# Power_block.net
KiCad netlist of a schematic drawn in Altium Designer
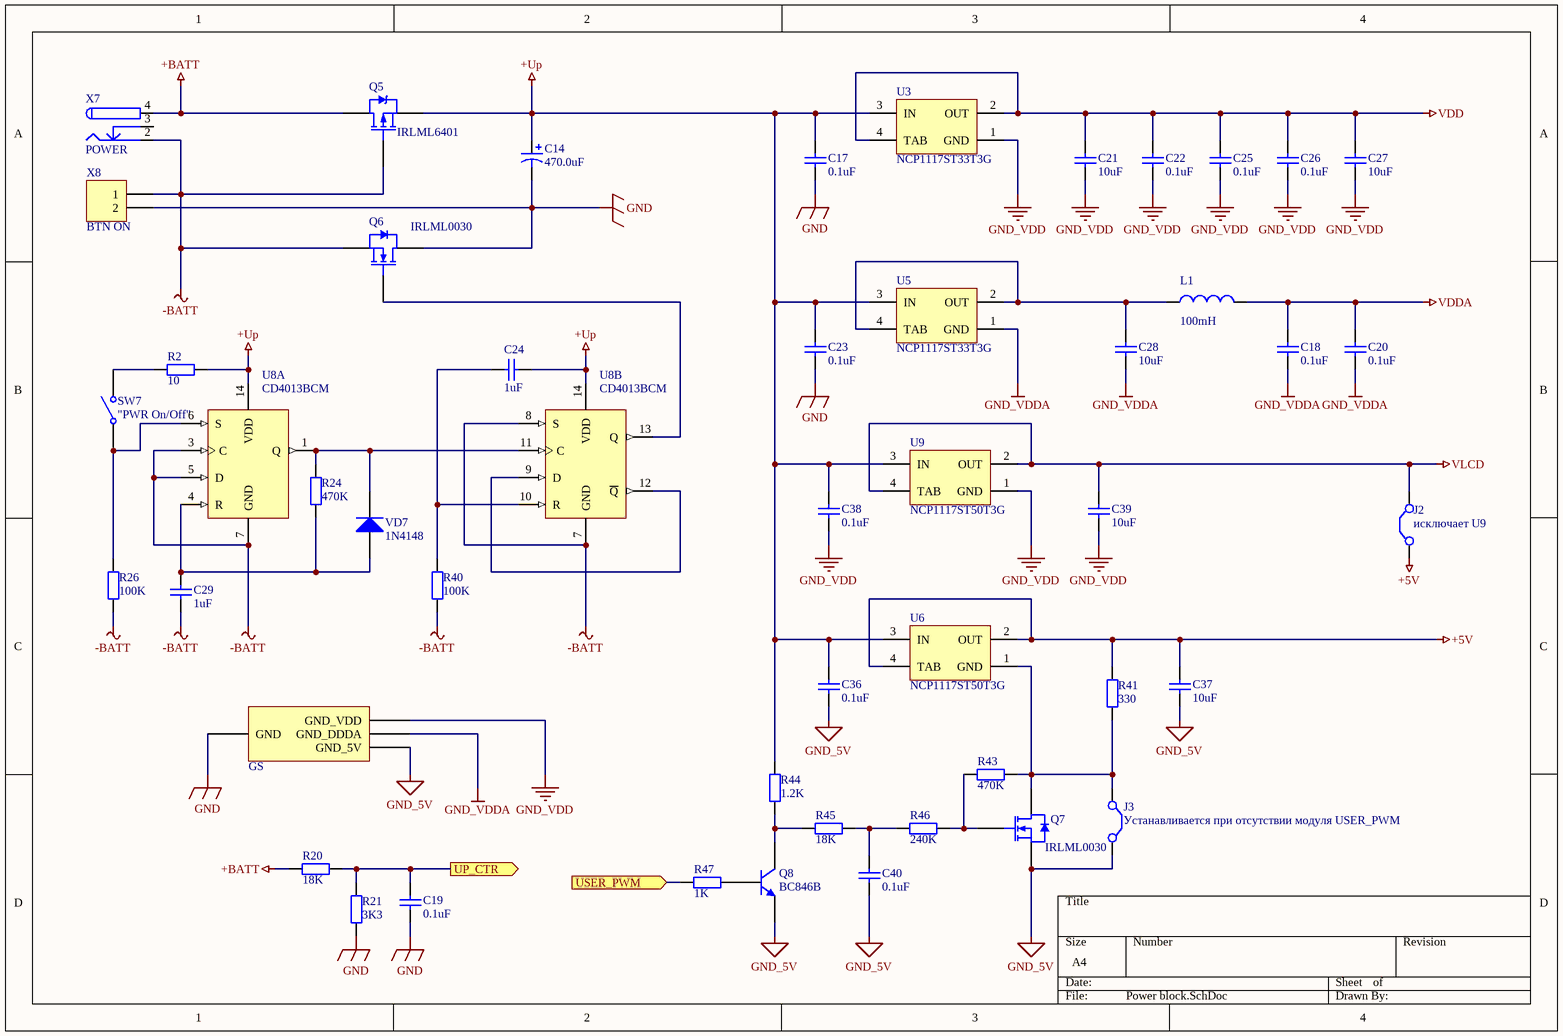
[diagram p0: Power block.SchDoc]

(export (version "E")
  (design (tool "Eeschema 10.0.6"))
  (components
    (comp (ref "C14")
      (value "470.0uF")
      (footprint "Capacitor-10x12.5-lyingR")
      (description "Polarized Capacitor (Radial)")
      (fields (field (name "PUBLISHER") "Altium Limited"))
      (libsource (lib "Quasar ARM") (part "Cap Pol1"))
    )
    (comp (ref "C17")
      (value "0.1uF")
      (footprint "1206_SMD_Capacitor")
      (description "Capacitor")
      (fields (field (name "PUBLISHER") "Altium Limited"))
      (libsource (lib "Quasar ARM") (part "Capacitor SMD"))
    )
    (comp (ref "C18")
      (value "0.1uF")
      (footprint "1206_SMD_Capacitor")
      (description "Capacitor")
      (fields (field (name "PUBLISHER") "Altium Limited"))
      (libsource (lib "Quasar ARM") (part "Capacitor SMD"))
    )
    (comp (ref "C19")
      (value "0.1uF")
      (footprint "1206_SMD_Capacitor")
      (description "Capacitor")
      (fields (field (name "PUBLISHER") "Altium Limited"))
      (libsource (lib "Quasar ARM") (part "Capacitor SMD"))
    )
    (comp (ref "C20")
      (value "0.1uF")
      (footprint "1206_SMD_Capacitor")
      (description "Capacitor")
      (fields (field (name "PUBLISHER") "Altium Limited"))
      (libsource (lib "Quasar ARM") (part "Capacitor SMD"))
    )
    (comp (ref "C21")
      (value "10uF")
      (footprint "1206_SMD_Capacitor")
      (description "Capacitor")
      (fields (field (name "PUBLISHER") "Altium Limited"))
      (libsource (lib "Quasar ARM") (part "Capacitor SMD"))
    )
    (comp (ref "C22")
      (value "0.1uF")
      (footprint "0805")
      (description "Capacitor")
      (fields (field (name "PUBLISHER") "Altium Limited"))
      (libsource (lib "Quasar ARM") (part "Capacitor SMD"))
    )
    (comp (ref "C23")
      (value "0.1uF")
      (footprint "1206_SMD_Capacitor")
      (description "Capacitor")
      (fields (field (name "PUBLISHER") "Altium Limited"))
      (libsource (lib "Quasar ARM") (part "Capacitor SMD"))
    )
    (comp (ref "C24")
      (value "1uF")
      (footprint "1206_SMD_Capacitor")
      (description "Capacitor")
      (fields (field (name "PUBLISHER") "Altium Limited"))
      (libsource (lib "Quasar ARM") (part "Capacitor SMD"))
    )
    (comp (ref "C25")
      (value "0.1uF")
      (footprint "0805")
      (description "Capacitor")
      (fields (field (name "PUBLISHER") "Altium Limited"))
      (libsource (lib "Quasar ARM") (part "Capacitor SMD"))
    )
    (comp (ref "C26")
      (value "0.1uF")
      (footprint "0805")
      (description "Capacitor")
      (fields (field (name "PUBLISHER") "Altium Limited"))
      (libsource (lib "Quasar ARM") (part "Capacitor SMD"))
    )
    (comp (ref "C27")
      (value "10uF")
      (footprint "1206_SMD_Capacitor")
      (description "Capacitor")
      (fields (field (name "PUBLISHER") "Altium Limited"))
      (libsource (lib "Quasar ARM") (part "Capacitor SMD"))
    )
    (comp (ref "C28")
      (value "10uF")
      (footprint "1206_SMD_Capacitor")
      (description "Capacitor")
      (fields (field (name "PUBLISHER") "Altium Limited"))
      (libsource (lib "Quasar ARM") (part "Capacitor SMD"))
    )
    (comp (ref "C29")
      (value "1uF")
      (footprint "1206_SMD_Capacitor")
      (description "Capacitor")
      (fields (field (name "PUBLISHER") "Altium Limited"))
      (libsource (lib "Quasar ARM") (part "Capacitor SMD"))
    )
    (comp (ref "C36")
      (value "0.1uF")
      (footprint "1206_SMD_Capacitor")
      (description "Capacitor")
      (fields (field (name "PUBLISHER") "Altium Limited"))
      (libsource (lib "Quasar ARM") (part "Capacitor SMD"))
    )
    (comp (ref "C37")
      (value "10uF")
      (footprint "1206_SMD_Capacitor")
      (description "Capacitor")
      (fields (field (name "PUBLISHER") "Altium Limited"))
      (libsource (lib "Quasar ARM") (part "Capacitor SMD"))
    )
    (comp (ref "C38")
      (value "0.1uF")
      (footprint "1206_SMD_Capacitor")
      (description "Capacitor")
      (fields (field (name "PUBLISHER") "Altium Limited"))
      (libsource (lib "Quasar ARM") (part "Capacitor SMD"))
    )
    (comp (ref "C39")
      (value "10uF")
      (footprint "1206_SMD_Capacitor")
      (description "Capacitor")
      (fields (field (name "PUBLISHER") "Altium Limited"))
      (libsource (lib "Quasar ARM") (part "Capacitor SMD"))
    )
    (comp (ref "C40")
      (value "0.1uF")
      (footprint "1206_SMD_Capacitor")
      (description "Capacitor")
      (fields (field (name "PUBLISHER") "Altium Limited"))
      (libsource (lib "Quasar ARM") (part "Capacitor SMD"))
    )
    (comp (ref "GS")
      (value "Ground setter")
      (footprint "GND_POINT")
      (libsource (lib "Quasar ARM") (part "Ground setter"))
    )
    (comp (ref "J2")
      (value "исключает U9")
      (footprint "1206_SMD_JUMPER")
      (description "Jumper Wire")
      (fields (field (name "PUBLISHER") "Altium Limited"))
      (libsource (lib "Quasar ARM") (part "Jumper"))
    )
    (comp (ref "J3")
      (value "Устанавливается при отсутствии модуля USER_PWM")
      (footprint "1206_SMD_Resistor")
      (description "Jumper Wire")
      (fields (field (name "PUBLISHER") "Altium Limited"))
      (libsource (lib "Quasar ARM") (part "Jumper"))
    )
    (comp (ref "L1")
      (value "100mH")
      (footprint "1210")
      (description "Inductor")
      (fields (field (name "PUBLISHER") "Altium Limited"))
      (libsource (lib "Quasar ARM") (part "Inductor"))
    )
    (comp (ref "Q5")
      (value "IRLML6401")
      (footprint "SOT23_N")
      (description "HEXFET Power MOSFET")
      (fields (field (name "PUBLISHER") "Altium Limited"))
      (libsource (lib "Quasar ARM") (part "IRLML6401"))
    )
    (comp (ref "Q6")
      (value "IRLML0030")
      (footprint "SOT23_N")
      (description "HEXFET Power MOSFET")
      (fields (field (name "PUBLISHER") "Altium Limited"))
      (libsource (lib "Quasar ARM") (part "2N7002"))
    )
    (comp (ref "Q7")
      (value "IRLML0030")
      (footprint "SOT23_N")
      (description "HEXFET Power MOSFET")
      (fields (field (name "PUBLISHER") "Altium Limited"))
      (libsource (lib "Quasar ARM") (part "2N7002"))
    )
    (comp (ref "Q8")
      (value "BC846B")
      (footprint "SOT23_N")
      (description "NPN General-purpose Transistor")
      (fields (field (name "PUBLISHER") "Altium Limited"))
      (libsource (lib "Quasar ARM") (part "BC846B"))
    )
    (comp (ref "R2")
      (value "10")
      (footprint "1206_SMD_Resistor")
      (description "Resistor")
      (fields (field (name "PUBLISHER") "Dmitry Kuzmin"))
      (libsource (lib "") (part "Resistor_1"))
    )
    (comp (ref "R20")
      (value "18K")
      (footprint "1206_SMD_Resistor")
      (description "Resistor")
      (fields (field (name "PUBLISHER") "Altium Limited"))
      (libsource (lib "") (part "Resistor_1"))
    )
    (comp (ref "R21")
      (value "3K3")
      (footprint "1206_SMD_Resistor")
      (description "Resistor")
      (fields (field (name "PUBLISHER") "Altium Limited"))
      (libsource (lib "") (part "Resistor_2"))
    )
    (comp (ref "R24")
      (value "470K")
      (footprint "1206_SMD_Resistor")
      (description "Resistor")
      (fields (field (name "PUBLISHER") "Dmitry Kuzmin"))
      (libsource (lib "") (part "Resistor_2"))
    )
    (comp (ref "R26")
      (value "100K")
      (footprint "1206_SMD_Resistor")
      (description "Resistor")
      (fields (field (name "PUBLISHER") "Dmitry Kuzmin"))
      (libsource (lib "") (part "Resistor_2"))
    )
    (comp (ref "R40")
      (value "100K")
      (footprint "1206_SMD_Resistor")
      (description "Resistor")
      (fields (field (name "PUBLISHER") "Dmitry Kuzmin"))
      (libsource (lib "") (part "Resistor_2"))
    )
    (comp (ref "R41")
      (value "330")
      (footprint "1206_SMD_Resistor")
      (description "Resistor")
      (fields (field (name "PUBLISHER") "Dmitry Kuzmin"))
      (libsource (lib "") (part "Resistor_2"))
    )
    (comp (ref "R43")
      (value "470K")
      (footprint "1206_SMD_Resistor")
      (description "Resistor")
      (fields (field (name "PUBLISHER") "Dmitry Kuzmin"))
      (libsource (lib "Quasar ARM") (part "Resistor"))
    )
    (comp (ref "R44")
      (value "1.2K")
      (footprint "1206_SMD_Resistor")
      (description "Resistor")
      (fields (field (name "PUBLISHER") "Dmitry Kuzmin"))
      (libsource (lib "") (part "Resistor_2"))
    )
    (comp (ref "R45")
      (value "18K")
      (footprint "1206_SMD_Resistor")
      (description "Resistor")
      (fields (field (name "PUBLISHER") "Dmitry Kuzmin"))
      (libsource (lib "") (part "Resistor_1"))
    )
    (comp (ref "R46")
      (value "240K")
      (footprint "1206_SMD_Resistor")
      (description "Resistor")
      (fields (field (name "PUBLISHER") "Dmitry Kuzmin"))
      (libsource (lib "") (part "Resistor_1"))
    )
    (comp (ref "R47")
      (value "1K")
      (footprint "1206_SMD_Resistor")
      (description "Resistor")
      (fields (field (name "PUBLISHER") "Dmitry Kuzmin"))
      (libsource (lib "") (part "Resistor_1"))
    )
    (comp (ref "SW7")
      (value "\"PWR On/Off\"")
      (footprint "KAN1211")
      (description "Single-Pole, Single-Throw Switch")
      (fields (field (name "PUBLISHER") "Altium Limited"))
      (libsource (lib "Quasar ARM") (part "TACT Switch"))
    )
    (comp (ref "U3")
      (value "NCP1117ST33T3G")
      (footprint "SOT-223")
      (description "LDO стабилизатор 3.3 V, 1 A, падение 1.2 V, Uвх до 20 V, 0..+125°C, 1%")
      (fields
        (field (name "PARTNUMBER") "LM1117S-3.3")
        (field (name "MANUFACTURER") "National Semiconductor")
        (field (name "PUBLISHER") "Altium Limited")
      )
      (libsource (lib "Quasar ARM_1") (part "NCP1117ST33"))
    )
    (comp (ref "U5")
      (value "NCP1117ST33T3G")
      (footprint "SOT-223")
      (description "LDO стабилизатор 3.3 V, 1 A, падение 1.2 V, Uвх до 20 V, 0..+125°C, 1%")
      (fields
        (field (name "PARTNUMBER") "LM1117S-3.3")
        (field (name "MANUFACTURER") "National Semiconductor")
        (field (name "PUBLISHER") "Altium Limited")
      )
      (libsource (lib "Quasar ARM_1") (part "NCP1117ST33"))
    )
    (comp (ref "U6")
      (value "NCP1117ST50T3G")
      (footprint "SOT-223")
      (description "LDO стабилизатор 5.0 V, 1 A, падение 1.2 V, Uвх до 20 V, 0..+125°C, 1%")
      (fields
        (field (name "PARTNUMBER") "LM1117S-5.0")
        (field (name "MANUFACTURER") "National Semiconductor")
        (field (name "PUBLISHER") "Altium Limited")
      )
      (libsource (lib "Quasar ARM_1") (part "NCP1117ST50"))
    )
    (comp (ref "U8")
      (value "CD4013BCM")
      (footprint "M14A_M")
      (description "Dual D-Type Flip-Flop")
      (fields (field (name "PUBLISHER") "Altium Limited"))
      (libsource (lib "") (part "CD4013BCM_1"))
    )
    (comp (ref "U9")
      (value "NCP1117ST50T3G")
      (footprint "SOT-223")
      (description "LDO стабилизатор 5.0 V, 1 A, падение 1.2 V, Uвх до 20 V, 0..+125°C, 1%")
      (fields
        (field (name "PARTNUMBER") "LM1117S-5.0")
        (field (name "MANUFACTURER") "National Semiconductor")
        (field (name "PUBLISHER") "Altium Limited")
      )
      (libsource (lib "Quasar ARM_1") (part "NCP1117ST50"))
    )
    (comp (ref "VD7")
      (value "1N4148")
      (footprint "SOD-323")
      (description "High Conductance Fast Diode")
      (fields (field (name "PUBLISHER") "Altium Limited"))
      (libsource (lib "Quasar ARM") (part "1N4148"))
    )
    (comp (ref "X7")
      (value "POWER")
      (footprint "DC-044")
      (description "Low Voltage Power Supply Connector")
      (fields (field (name "PUBLISHER") "Altium Limited"))
      (libsource (lib "Quasar ARM") (part "DC-044"))
    )
    (comp (ref "X8")
      (value "BTN ON")
      (footprint "HDR1X2")
      (description "Header, 2-Pin")
      (fields (field (name "PUBLISHER") "Altium Limited"))
      (libsource (lib "Quasar ARM") (part "Header 2"))
    )
  )
  (nets
    (net (code "1") (name "+5V") (class "Default")
      (node (ref "C37") (pin "2") (pinfunction "2_2") (pintype "passive"))
      (node (ref "J2") (pin "1") (pinfunction "C1_1") (pintype "passive"))
      (node (ref "R41") (pin "2") (pinfunction "2_2") (pintype "passive"))
      (node (ref "U6") (pin "2") (pinfunction "OUT_2") (pintype "power_in"))
      (node (ref "U6") (pin "4") (pinfunction "TAB_4") (pintype "power_in"))
    )
    (net (code "2") (name "+BATT") (class "Default")
      (node (ref "Q5") (pin "3") (pinfunction "D_3") (pintype "passive"))
      (node (ref "R20") (pin "1") (pinfunction "1_1") (pintype "passive"))
      (node (ref "X7") (pin "4") (pinfunction "4_4") (pintype "power_in"))
    )
    (net (code "3") (name "+Up") (class "Default")
      (node (ref "C14") (pin "1") (pinfunction "1_1") (pintype "passive"))
      (node (ref "C17") (pin "2") (pinfunction "2_2") (pintype "passive"))
      (node (ref "C23") (pin "2") (pinfunction "2_2") (pintype "passive"))
      (node (ref "C24") (pin "2") (pinfunction "2_2") (pintype "passive"))
      (node (ref "C36") (pin "2") (pinfunction "2_2") (pintype "passive"))
      (node (ref "C38") (pin "2") (pinfunction "2_2") (pintype "passive"))
      (node (ref "Q5") (pin "2") (pinfunction "S_2") (pintype "passive"))
      (node (ref "R2") (pin "2") (pinfunction "2_2") (pintype "passive"))
      (node (ref "R44") (pin "2") (pinfunction "2_2") (pintype "passive"))
      (node (ref "U3") (pin "3") (pinfunction "IN_3") (pintype "power_in"))
      (node (ref "U5") (pin "3") (pinfunction "IN_3") (pintype "power_in"))
      (node (ref "U6") (pin "3") (pinfunction "IN_3") (pintype "power_in"))
      (node (ref "U8") (pin "14") (pinfunction "VDD_14") (pintype "power_in"))
      (node (ref "U9") (pin "3") (pinfunction "IN_3") (pintype "power_in"))
    )
    (net (code "4") (name "-BATT") (class "Default")
      (node (ref "C29") (pin "1") (pinfunction "1_1") (pintype "passive"))
      (node (ref "Q5") (pin "1") (pinfunction "G_1") (pintype "passive"))
      (node (ref "Q6") (pin "2") (pinfunction "S_2") (pintype "passive"))
      (node (ref "R26") (pin "1") (pinfunction "1_1") (pintype "passive"))
      (node (ref "R40") (pin "1") (pinfunction "1_1") (pintype "passive"))
      (node (ref "U8") (pin "3") (pinfunction "C_3") (pintype "input"))
      (node (ref "U8") (pin "5") (pinfunction "D_5") (pintype "input"))
      (node (ref "U8") (pin "7") (pinfunction "GND_7") (pintype "power_in"))
      (node (ref "U8") (pin "8") (pinfunction "S_8") (pintype "input"))
      (node (ref "X7") (pin "2") (pinfunction "2_2") (pintype "power_in"))
      (node (ref "X8") (pin "1") (pinfunction "1_1") (pintype "passive"))
    )
    (net (code "5") (name "/UP_CTR") (class "Default")
      (node (ref "C19") (pin "2") (pinfunction "2_2") (pintype "passive"))
      (node (ref "R20") (pin "2") (pinfunction "2_2") (pintype "passive"))
      (node (ref "R21") (pin "2") (pinfunction "2_2") (pintype "passive"))
    )
    (net (code "6") (name "/USER_PWM") (class "Default")
      (node (ref "R47") (pin "1") (pinfunction "1_1") (pintype "passive"))
    )
    (net (code "7") (name "GND") (class "Default")
      (node (ref "C14") (pin "2") (pinfunction "2_2") (pintype "passive"))
      (node (ref "C17") (pin "1") (pinfunction "1_1") (pintype "passive"))
      (node (ref "C19") (pin "1") (pinfunction "1_1") (pintype "passive"))
      (node (ref "C23") (pin "1") (pinfunction "1_1") (pintype "passive"))
      (node (ref "GS") (pin "1") (pinfunction "GND_1") (pintype "passive"))
      (node (ref "Q6") (pin "3") (pinfunction "D_3") (pintype "passive"))
      (node (ref "R21") (pin "1") (pinfunction "1_1") (pintype "passive"))
      (node (ref "X8") (pin "2") (pinfunction "2_2") (pintype "passive"))
    )
    (net (code "8") (name "GND_5V") (class "Default")
      (node (ref "C36") (pin "1") (pinfunction "1_1") (pintype "passive"))
      (node (ref "C37") (pin "1") (pinfunction "1_1") (pintype "passive"))
      (node (ref "C40") (pin "1") (pinfunction "1_1") (pintype "passive"))
      (node (ref "GS") (pin "4") (pinfunction "GND_5V_4") (pintype "passive"))
      (node (ref "J3") (pin "2") (pinfunction "C2_2") (pintype "passive"))
      (node (ref "Q7") (pin "2") (pinfunction "S_2") (pintype "passive"))
      (node (ref "Q8") (pin "2") (pinfunction "E_2") (pintype "passive"))
    )
    (net (code "9") (name "GND_VDD") (class "Default")
      (node (ref "C21") (pin "1") (pinfunction "1_1") (pintype "passive"))
      (node (ref "C22") (pin "1") (pinfunction "1_1") (pintype "passive"))
      (node (ref "C25") (pin "1") (pinfunction "1_1") (pintype "passive"))
      (node (ref "C26") (pin "1") (pinfunction "1_1") (pintype "passive"))
      (node (ref "C27") (pin "1") (pinfunction "1_1") (pintype "passive"))
      (node (ref "C38") (pin "1") (pinfunction "1_1") (pintype "passive"))
      (node (ref "C39") (pin "1") (pinfunction "1_1") (pintype "passive"))
      (node (ref "GS") (pin "2") (pinfunction "GND_VDD_2") (pintype "passive"))
      (node (ref "U3") (pin "1") (pinfunction "GND_1") (pintype "power_in"))
      (node (ref "U9") (pin "1") (pinfunction "GND_1") (pintype "power_in"))
    )
    (net (code "10") (name "GND_VDDA") (class "Default")
      (node (ref "C18") (pin "1") (pinfunction "1_1") (pintype "passive"))
      (node (ref "C20") (pin "1") (pinfunction "1_1") (pintype "passive"))
      (node (ref "C28") (pin "1") (pinfunction "1_1") (pintype "passive"))
      (node (ref "GS") (pin "3") (pinfunction "GND_DDDA_3") (pintype "passive"))
      (node (ref "U5") (pin "1") (pinfunction "GND_1") (pintype "power_in"))
    )
    (net (code "11") (name "Net-(C40-Pad2)") (class "Default")
      (node (ref "C40") (pin "2") (pinfunction "2_2") (pintype "passive"))
      (node (ref "R45") (pin "2") (pinfunction "2_2") (pintype "passive"))
      (node (ref "R46") (pin "1") (pinfunction "1_1") (pintype "passive"))
    )
    (net (code "12") (name "Net-(J3-C1)") (class "Default")
      (node (ref "J3") (pin "1") (pinfunction "C1_1") (pintype "passive"))
      (node (ref "Q7") (pin "3") (pinfunction "D_3") (pintype "passive"))
      (node (ref "R41") (pin "1") (pinfunction "1_1") (pintype "passive"))
      (node (ref "R43") (pin "1") (pinfunction "1_1") (pintype "passive"))
      (node (ref "U6") (pin "1") (pinfunction "GND_1") (pintype "power_in"))
    )
    (net (code "13") (name "Net-(Q6-G)") (class "Default")
      (node (ref "Q6") (pin "1") (pinfunction "G_1") (pintype "passive"))
      (node (ref "U8") (pin "13") (pinfunction "Q_13") (pintype "output"))
    )
    (net (code "14") (name "Net-(Q7-G)") (class "Default")
      (node (ref "Q7") (pin "1") (pinfunction "G_1") (pintype "passive"))
      (node (ref "R43") (pin "2") (pinfunction "2_2") (pintype "passive"))
      (node (ref "R46") (pin "2") (pinfunction "2_2") (pintype "passive"))
    )
    (net (code "15") (name "Net-(Q8-B)") (class "Default")
      (node (ref "Q8") (pin "1") (pinfunction "B_1") (pintype "passive"))
      (node (ref "R47") (pin "2") (pinfunction "2_2") (pintype "passive"))
    )
    (net (code "16") (name "Net-(Q8-C)") (class "Default")
      (node (ref "Q8") (pin "3") (pinfunction "C_3") (pintype "passive"))
      (node (ref "R44") (pin "1") (pinfunction "1_1") (pintype "passive"))
      (node (ref "R45") (pin "1") (pinfunction "1_1") (pintype "passive"))
    )
    (net (code "17") (name "Net-(SW7-COMMON)") (class "Default")
      (node (ref "R26") (pin "2") (pinfunction "2_2") (pintype "passive"))
      (node (ref "SW7") (pin "1") (pinfunction "COMMON_1") (pintype "passive"))
      (node (ref "U8") (pin "6") (pinfunction "S_6") (pintype "input"))
    )
    (net (code "18") (name "Net-(SW7-NO)") (class "Default")
      (node (ref "R2") (pin "1") (pinfunction "1_1") (pintype "passive"))
      (node (ref "SW7") (pin "2") (pinfunction "NO_2") (pintype "passive"))
    )
    (net (code "19") (name "Net-(U5-OUT)") (class "Default")
      (node (ref "C28") (pin "2") (pinfunction "2_2") (pintype "passive"))
      (node (ref "L1") (pin "1") (pinfunction "1_1") (pintype "passive"))
      (node (ref "U5") (pin "2") (pinfunction "OUT_2") (pintype "power_in"))
      (node (ref "U5") (pin "4") (pinfunction "TAB_4") (pintype "power_in"))
    )
    (net (code "20") (name "Net-(U8A-Q)") (class "Default")
      (node (ref "R24") (pin "2") (pinfunction "2_2") (pintype "passive"))
      (node (ref "U8") (pin "1") (pinfunction "Q_1") (pintype "output"))
      (node (ref "U8") (pin "11") (pinfunction "C_11") (pintype "input"))
      (node (ref "VD7") (pin "2") (pinfunction "K_2") (pintype "passive"))
    )
    (net (code "21") (name "Net-(U8A-R)") (class "Default")
      (node (ref "C29") (pin "2") (pinfunction "2_2") (pintype "passive"))
      (node (ref "R24") (pin "1") (pinfunction "1_1") (pintype "passive"))
      (node (ref "U8") (pin "4") (pinfunction "R_4") (pintype "input"))
      (node (ref "VD7") (pin "1") (pinfunction "A_1") (pintype "passive"))
    )
    (net (code "22") (name "Net-(U8B-D)") (class "Default")
      (node (ref "U8") (pin "12") (pinfunction "~{Q}_12") (pintype "output"))
      (node (ref "U8") (pin "9") (pinfunction "D_9") (pintype "input"))
    )
    (net (code "23") (name "Net-(U8B-R)") (class "Default")
      (node (ref "C24") (pin "1") (pinfunction "1_1") (pintype "passive"))
      (node (ref "R40") (pin "2") (pinfunction "2_2") (pintype "passive"))
      (node (ref "U8") (pin "10") (pinfunction "R_10") (pintype "input"))
    )
    (net (code "24") (name "VDD") (class "Default")
      (node (ref "C21") (pin "2") (pinfunction "2_2") (pintype "passive"))
      (node (ref "C22") (pin "2") (pinfunction "2_2") (pintype "passive"))
      (node (ref "C25") (pin "2") (pinfunction "2_2") (pintype "passive"))
      (node (ref "C26") (pin "2") (pinfunction "2_2") (pintype "passive"))
      (node (ref "C27") (pin "2") (pinfunction "2_2") (pintype "passive"))
      (node (ref "U3") (pin "2") (pinfunction "OUT_2") (pintype "power_in"))
      (node (ref "U3") (pin "4") (pinfunction "TAB_4") (pintype "power_in"))
    )
    (net (code "25") (name "VDDA") (class "Default")
      (node (ref "C18") (pin "2") (pinfunction "2_2") (pintype "passive"))
      (node (ref "C20") (pin "2") (pinfunction "2_2") (pintype "passive"))
      (node (ref "L1") (pin "2") (pinfunction "2_2") (pintype "passive"))
    )
    (net (code "26") (name "VLCD") (class "Default")
      (node (ref "C39") (pin "2") (pinfunction "2_2") (pintype "passive"))
      (node (ref "J2") (pin "2") (pinfunction "C2_2") (pintype "passive"))
      (node (ref "U9") (pin "2") (pinfunction "OUT_2") (pintype "power_in"))
      (node (ref "U9") (pin "4") (pinfunction "TAB_4") (pintype "power_in"))
    )
    (net (code "27") (name "unconnected-(U8A-~{Q}-Pad2)") (class "Default")
      (node (ref "U8") (pin "2") (pinfunction "~{Q}_2") (pintype "output"))
    )
    (net (code "28") (name "unconnected-(X7-Pad3)") (class "Default")
      (node (ref "X7") (pin "3") (pinfunction "3_3") (pintype "power_in"))
    )
  )
)
